# MyoMain.net
KiCad netlist of a schematic drawn in EAGLE
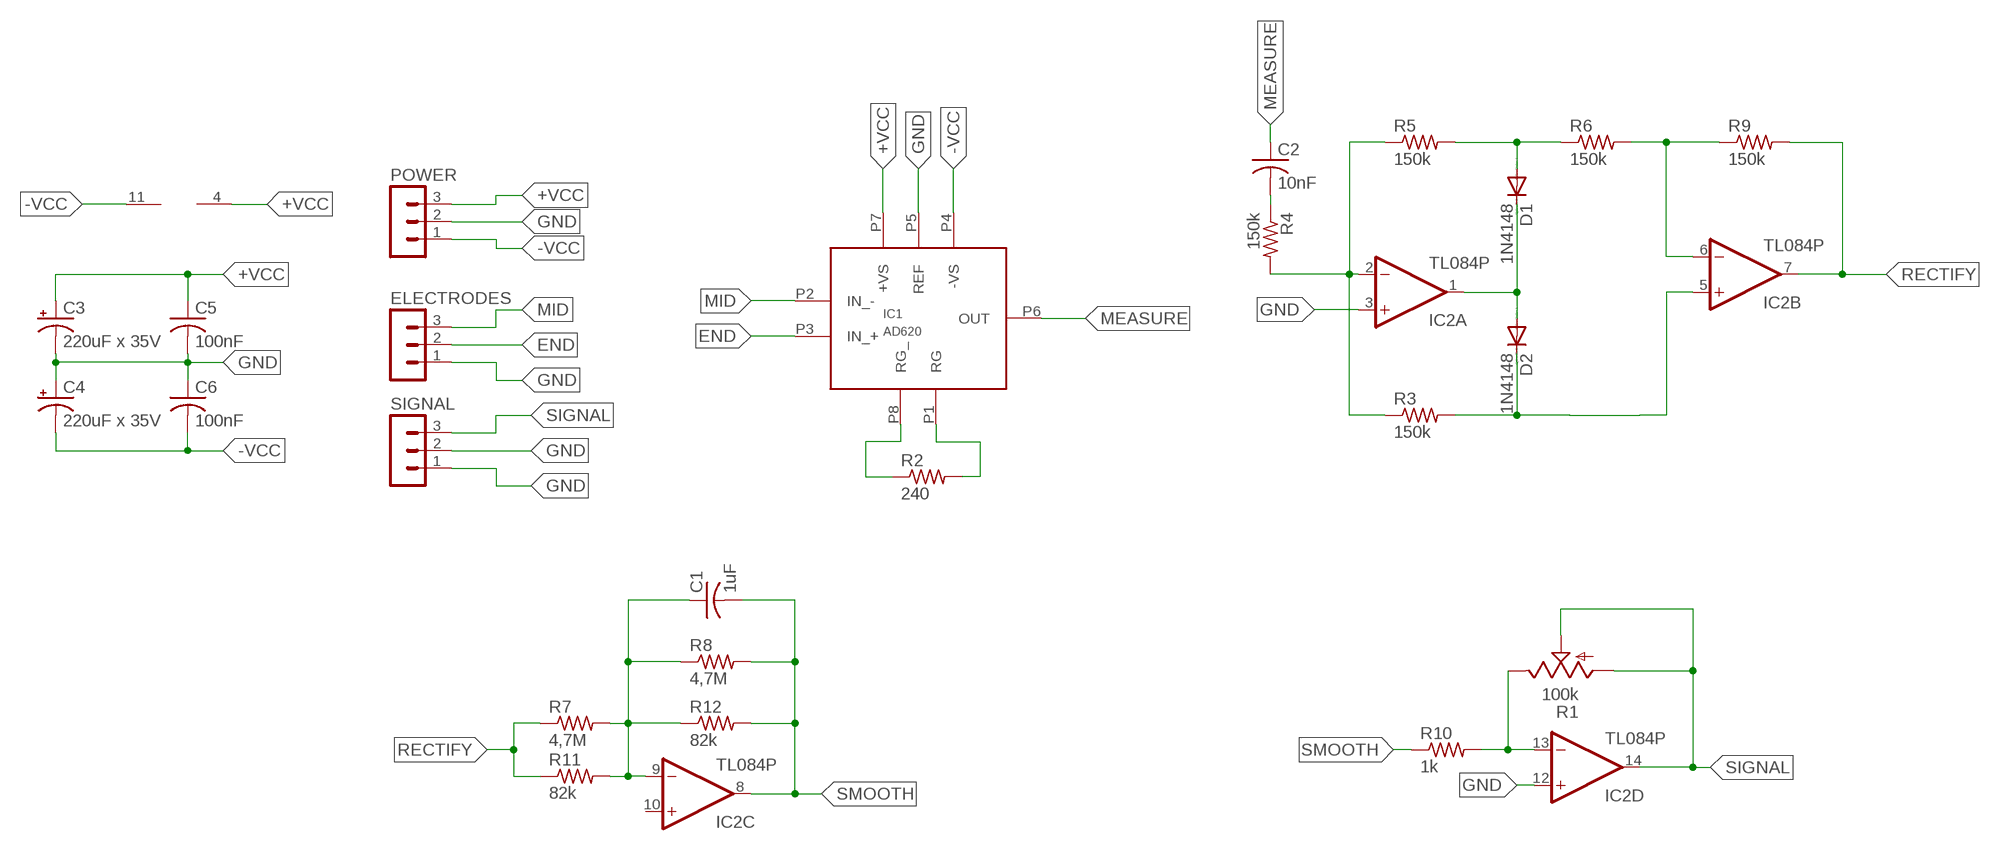
[diagram p0: schematic, sheet 1]

(export (version "E")
  (design (tool "Eeschema 10.0.6"))
  (components
    (comp (ref "C1")
      (value "1uF")
      (footprint "eagle-import:C025-025X050")
      (libsource (lib "eagle-import") (part "C-US025-025X050"))
    )
    (comp (ref "C2")
      (value "10nF")
      (footprint "eagle-import:C025-025X050")
      (libsource (lib "eagle-import") (part "C-US025-025X050"))
    )
    (comp (ref "C3")
      (value "220uF x 35V")
      (footprint "eagle-import:E3,5-10")
      (libsource (lib "eagle-import") (part "CPOL-USE3.5-10"))
    )
    (comp (ref "C4")
      (value "220uF x 35V")
      (footprint "eagle-import:E3,5-10")
      (libsource (lib "eagle-import") (part "CPOL-USE3.5-10"))
    )
    (comp (ref "C5")
      (value "100nF")
      (footprint "eagle-import:C025-025X050")
      (libsource (lib "eagle-import") (part "C-US025-025X050"))
    )
    (comp (ref "C6")
      (value "100nF")
      (footprint "eagle-import:C025-025X050")
      (libsource (lib "eagle-import") (part "C-US025-025X050"))
    )
    (comp (ref "D1")
      (value "1N4148")
      (footprint "eagle-import:DO35-10")
      (libsource (lib "eagle-import") (part "1N4148DO35-10"))
    )
    (comp (ref "D2")
      (value "1N4148")
      (footprint "eagle-import:DO35-10")
      (libsource (lib "eagle-import") (part "1N4148DO35-10"))
    )
    (comp (ref "ELECTRODES")
      (value "MA03-1")
      (footprint "eagle-import:MA03-1")
      (libsource (lib "eagle-import") (part "MA03-1"))
    )
    (comp (ref "IC1")
      (value "AD620")
      (footprint "eagle-import:DIL8")
      (libsource (lib "eagle-import") (part "AD620"))
    )
    (comp (ref "IC2")
      (value "TL084P")
      (footprint "eagle-import:DIL14")
      (libsource (lib "eagle-import") (part "TL084P"))
    )
    (comp (ref "POWER")
      (value "MA03-1")
      (footprint "eagle-import:MA03-1")
      (libsource (lib "eagle-import") (part "MA03-1"))
    )
    (comp (ref "R1")
      (value "100k")
      (footprint "eagle-import:S64W")
      (libsource (lib "eagle-import") (part "TRIM_US-S64W"))
    )
    (comp (ref "R2")
      (value "240")
      (footprint "eagle-import:0207_10")
      (libsource (lib "eagle-import") (part "R-US_0207/10"))
    )
    (comp (ref "R3")
      (value "150k")
      (footprint "eagle-import:0207_10")
      (libsource (lib "eagle-import") (part "R-US_0207/10"))
    )
    (comp (ref "R4")
      (value "150k")
      (footprint "eagle-import:0207_10")
      (libsource (lib "eagle-import") (part "R-US_0207/10"))
    )
    (comp (ref "R5")
      (value "150k")
      (footprint "eagle-import:0207_10")
      (libsource (lib "eagle-import") (part "R-US_0207/10"))
    )
    (comp (ref "R6")
      (value "150k")
      (footprint "eagle-import:0207_10")
      (libsource (lib "eagle-import") (part "R-US_0207/10"))
    )
    (comp (ref "R7")
      (value "4,7M")
      (footprint "eagle-import:0207_10")
      (libsource (lib "eagle-import") (part "R-US_0207/10"))
    )
    (comp (ref "R8")
      (value "4,7M")
      (footprint "eagle-import:0207_10")
      (libsource (lib "eagle-import") (part "R-US_0207/10"))
    )
    (comp (ref "R9")
      (value "150k")
      (footprint "eagle-import:0207_10")
      (libsource (lib "eagle-import") (part "R-US_0207/10"))
    )
    (comp (ref "R10")
      (value "1k")
      (footprint "eagle-import:0207_10")
      (libsource (lib "eagle-import") (part "R-US_0207/10"))
    )
    (comp (ref "R11")
      (value "82k")
      (footprint "eagle-import:0207_10")
      (libsource (lib "eagle-import") (part "R-US_0207/10"))
    )
    (comp (ref "R12")
      (value "82k")
      (footprint "eagle-import:0207_10")
      (libsource (lib "eagle-import") (part "R-US_0207/10"))
    )
    (comp (ref "SIGNAL")
      (value "MA03-1")
      (footprint "eagle-import:MA03-1")
      (libsource (lib "eagle-import") (part "MA03-1"))
    )
  )
  (nets
    (net (code "1") (name "+VCC") (class "Default")
      (node (ref "C3") (pin "+") (pinfunction "+_+") (pintype "passive"))
      (node (ref "C5") (pin "1") (pinfunction "1_1") (pintype "passive"))
      (node (ref "IC1") (pin "P7") (pinfunction "+VS_P7") (pintype "power_in"))
      (node (ref "IC2") (pin "4") (pinfunction "V+_4") (pintype "power_in"))
      (node (ref "POWER") (pin "3") (pinfunction "3_3") (pintype "passive"))
    )
    (net (code "2") (name "-VCC") (class "Default")
      (node (ref "C4") (pin "-") (pinfunction "-_-") (pintype "passive"))
      (node (ref "C6") (pin "2") (pinfunction "2_2") (pintype "passive"))
      (node (ref "IC1") (pin "P4") (pinfunction "-VS_P4") (pintype "power_in"))
      (node (ref "IC2") (pin "11") (pinfunction "V-_11") (pintype "power_in"))
      (node (ref "POWER") (pin "1") (pinfunction "1_1") (pintype "passive"))
    )
    (net (code "3") (name "END") (class "Default")
      (node (ref "ELECTRODES") (pin "2") (pinfunction "2_2") (pintype "passive"))
      (node (ref "IC1") (pin "P3") (pinfunction "IN_+_P3") (pintype "input"))
    )
    (net (code "4") (name "GND") (class "Default")
      (node (ref "C3") (pin "-") (pinfunction "-_-") (pintype "passive"))
      (node (ref "C4") (pin "+") (pinfunction "+_+") (pintype "passive"))
      (node (ref "C5") (pin "2") (pinfunction "2_2") (pintype "passive"))
      (node (ref "C6") (pin "1") (pinfunction "1_1") (pintype "passive"))
      (node (ref "ELECTRODES") (pin "1") (pinfunction "1_1") (pintype "passive"))
      (node (ref "IC1") (pin "P5") (pinfunction "REF_P5") (pintype "power_in"))
      (node (ref "IC2") (pin "12") (pinfunction "+IN_12") (pintype "input"))
      (node (ref "IC2") (pin "3") (pinfunction "+IN_3") (pintype "input"))
      (node (ref "POWER") (pin "2") (pinfunction "2_2") (pintype "passive"))
      (node (ref "SIGNAL") (pin "1") (pinfunction "1_1") (pintype "passive"))
      (node (ref "SIGNAL") (pin "2") (pinfunction "2_2") (pintype "passive"))
    )
    (net (code "5") (name "MEASURE") (class "Default")
      (node (ref "C2") (pin "1") (pinfunction "1_1") (pintype "passive"))
      (node (ref "IC1") (pin "P6") (pinfunction "OUT_P6") (pintype "output"))
    )
    (net (code "6") (name "MID") (class "Default")
      (node (ref "ELECTRODES") (pin "3") (pinfunction "3_3") (pintype "passive"))
      (node (ref "IC1") (pin "P2") (pinfunction "IN_-_P2") (pintype "input"))
    )
    (net (code "7") (name "Net-(C2-Pad2)") (class "Default")
      (node (ref "C2") (pin "2") (pinfunction "2_2") (pintype "passive"))
      (node (ref "R4") (pin "1") (pinfunction "1_1") (pintype "passive"))
    )
    (net (code "8") (name "Net-(D1-PadA)") (class "Default")
      (node (ref "D1") (pin "A") (pinfunction "A_A") (pintype "passive"))
      (node (ref "R5") (pin "2") (pinfunction "2_2") (pintype "passive"))
      (node (ref "R6") (pin "1") (pinfunction "1_1") (pintype "passive"))
    )
    (net (code "9") (name "Net-(IC1-RG)") (class "Default")
      (node (ref "IC1") (pin "P1") (pinfunction "RG_P1") (pintype "input"))
      (node (ref "R2") (pin "2") (pinfunction "2_2") (pintype "passive"))
    )
    (net (code "10") (name "Net-(IC1-RG_)") (class "Default")
      (node (ref "IC1") (pin "P8") (pinfunction "RG__P8") (pintype "input"))
      (node (ref "R2") (pin "1") (pinfunction "1_1") (pintype "passive"))
    )
    (net (code "11") (name "Net-(IC2A--IN)") (class "Default")
      (node (ref "IC2") (pin "2") (pinfunction "-IN_2") (pintype "input"))
      (node (ref "R3") (pin "1") (pinfunction "1_1") (pintype "passive"))
      (node (ref "R4") (pin "2") (pinfunction "2_2") (pintype "passive"))
      (node (ref "R5") (pin "1") (pinfunction "1_1") (pintype "passive"))
    )
    (net (code "12") (name "Net-(IC2A-OUT)") (class "Default")
      (node (ref "D1") (pin "C") (pinfunction "C_C") (pintype "passive"))
      (node (ref "D2") (pin "A") (pinfunction "A_A") (pintype "passive"))
      (node (ref "IC2") (pin "1") (pinfunction "OUT_1") (pintype "output"))
    )
    (net (code "13") (name "Net-(IC2B-+IN)") (class "Default")
      (node (ref "D2") (pin "C") (pinfunction "C_C") (pintype "passive"))
      (node (ref "IC2") (pin "5") (pinfunction "+IN_5") (pintype "input"))
      (node (ref "R3") (pin "2") (pinfunction "2_2") (pintype "passive"))
    )
    (net (code "14") (name "Net-(IC2B--IN)") (class "Default")
      (node (ref "IC2") (pin "6") (pinfunction "-IN_6") (pintype "input"))
      (node (ref "R6") (pin "2") (pinfunction "2_2") (pintype "passive"))
      (node (ref "R9") (pin "1") (pinfunction "1_1") (pintype "passive"))
    )
    (net (code "15") (name "Net-(IC2C--IN)") (class "Default")
      (node (ref "C1") (pin "1") (pinfunction "1_1") (pintype "passive"))
      (node (ref "IC2") (pin "9") (pinfunction "-IN_9") (pintype "input"))
      (node (ref "R11") (pin "2") (pinfunction "2_2") (pintype "passive"))
      (node (ref "R12") (pin "1") (pinfunction "1_1") (pintype "passive"))
      (node (ref "R7") (pin "2") (pinfunction "2_2") (pintype "passive"))
      (node (ref "R8") (pin "1") (pinfunction "1_1") (pintype "passive"))
    )
    (net (code "16") (name "Net-(IC2D--IN)") (class "Default")
      (node (ref "IC2") (pin "13") (pinfunction "-IN_13") (pintype "input"))
      (node (ref "R1") (pin "E") (pinfunction "E_E") (pintype "passive"))
      (node (ref "R10") (pin "2") (pinfunction "2_2") (pintype "passive"))
    )
    (net (code "17") (name "RECTIFY") (class "Default")
      (node (ref "IC2") (pin "7") (pinfunction "OUT_7") (pintype "output"))
      (node (ref "R11") (pin "1") (pinfunction "1_1") (pintype "passive"))
      (node (ref "R7") (pin "1") (pinfunction "1_1") (pintype "passive"))
      (node (ref "R9") (pin "2") (pinfunction "2_2") (pintype "passive"))
    )
    (net (code "18") (name "SIGNAL") (class "Default")
      (node (ref "IC2") (pin "14") (pinfunction "OUT_14") (pintype "output"))
      (node (ref "R1") (pin "A") (pinfunction "A_A") (pintype "passive"))
      (node (ref "R1") (pin "S") (pinfunction "S_S") (pintype "passive"))
      (node (ref "SIGNAL") (pin "3") (pinfunction "3_3") (pintype "passive"))
    )
    (net (code "19") (name "SMOOTH") (class "Default")
      (node (ref "C1") (pin "2") (pinfunction "2_2") (pintype "passive"))
      (node (ref "IC2") (pin "8") (pinfunction "OUT_8") (pintype "output"))
      (node (ref "R10") (pin "1") (pinfunction "1_1") (pintype "passive"))
      (node (ref "R12") (pin "2") (pinfunction "2_2") (pintype "passive"))
      (node (ref "R8") (pin "2") (pinfunction "2_2") (pintype "passive"))
    )
    (net (code "20") (name "unconnected-(IC2C-+IN-Pad10)") (class "Default")
      (node (ref "IC2") (pin "10") (pinfunction "+IN_10") (pintype "input"))
    )
  )
)
